# atmega16u2custom2.net
KiCad netlist of a schematic drawn in EAGLE
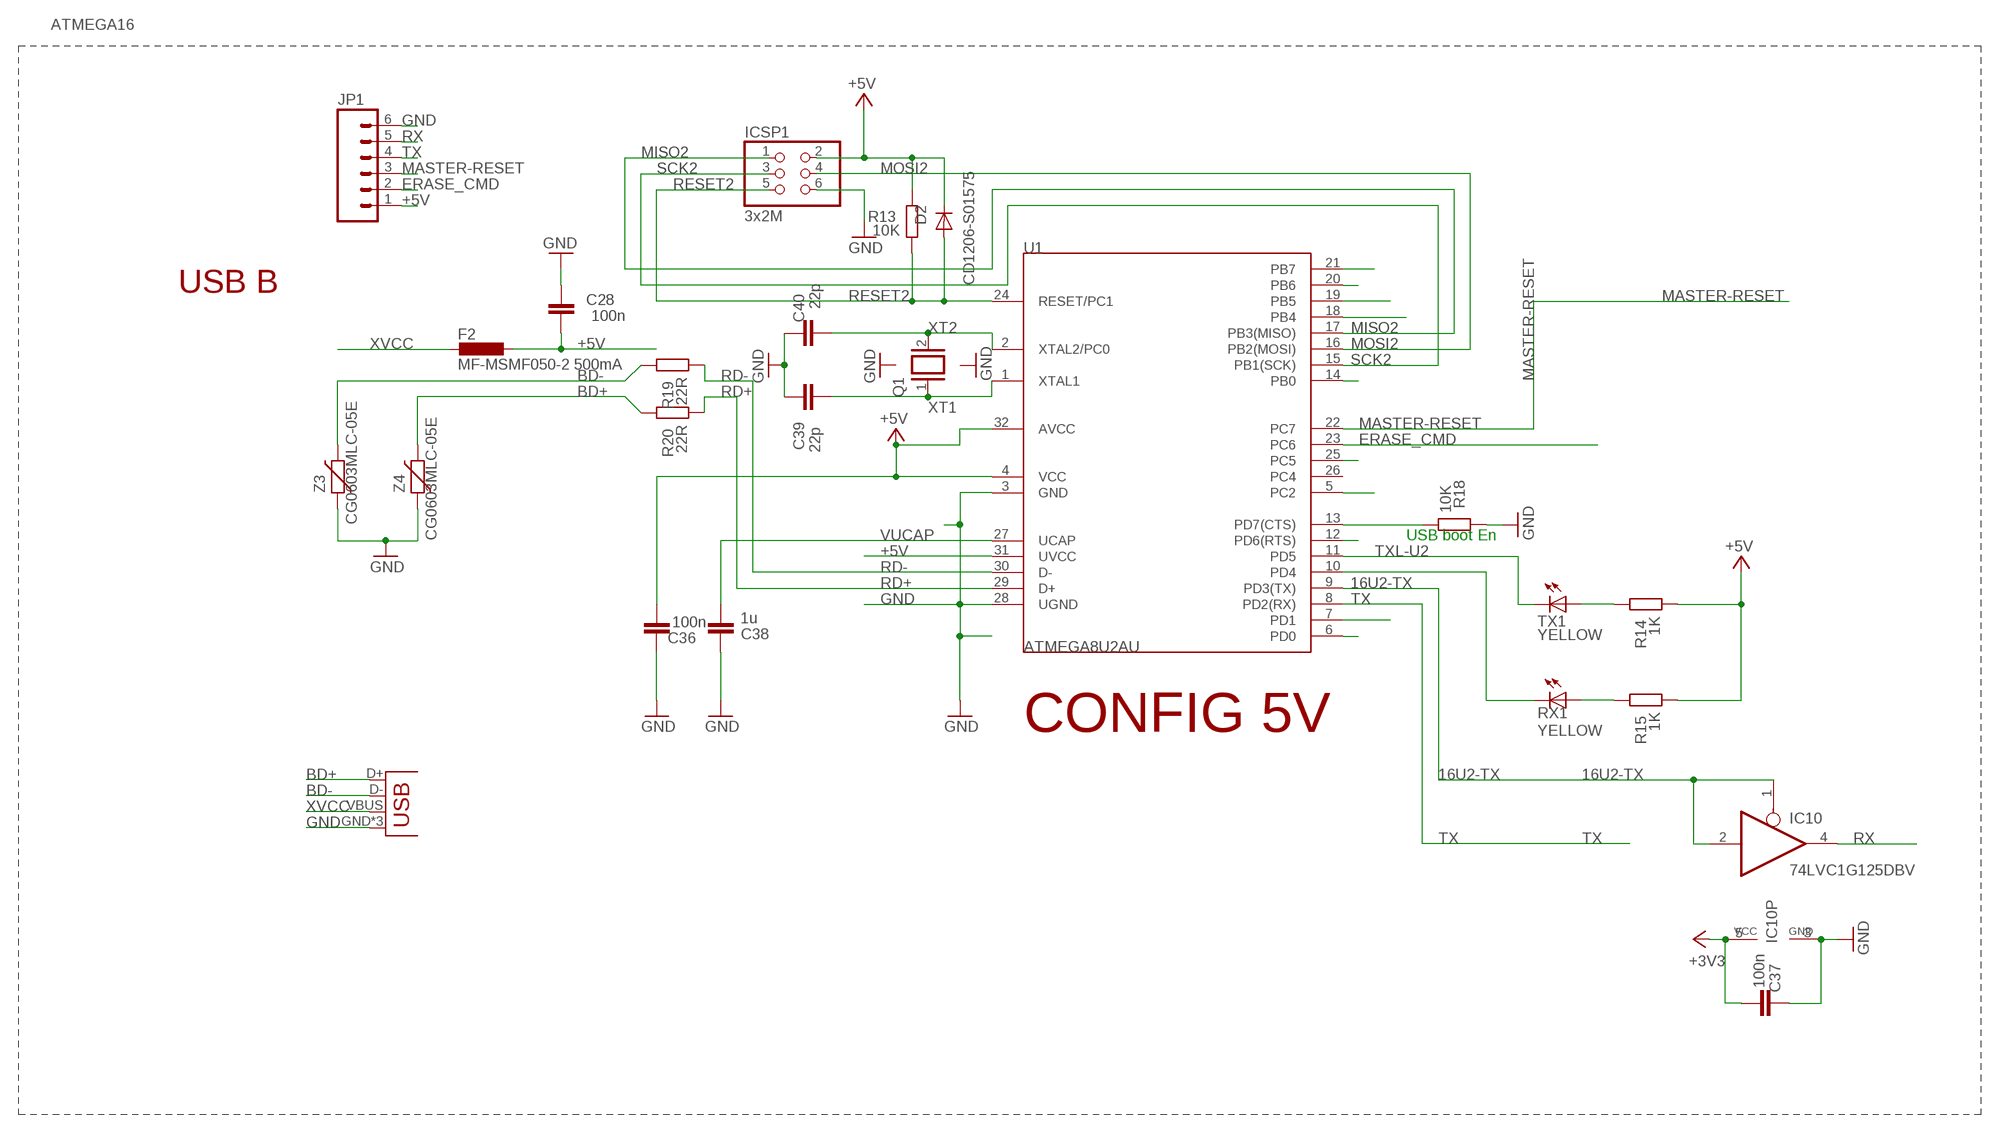
[diagram p0: schematic, sheet 1]

(export (version "E")
  (design (tool "Eeschema 10.0.6"))
  (components
    (comp (ref "C28")
      (value "100n")
      (footprint "eagle-import:C0805")
      (libsource (lib "eagle-import") (part "C-EUC0805"))
    )
    (comp (ref "C36")
      (value "100n")
      (footprint "eagle-import:C0805")
      (libsource (lib "eagle-import") (part "C-EUC0805"))
    )
    (comp (ref "C37")
      (value "100n")
      (footprint "eagle-import:C0805")
      (libsource (lib "eagle-import") (part "C-EUC0805"))
    )
    (comp (ref "C38")
      (value "1u")
      (footprint "eagle-import:C0805")
      (libsource (lib "eagle-import") (part "C-EUC0805"))
    )
    (comp (ref "C39")
      (value "22p")
      (footprint "eagle-import:C0805")
      (libsource (lib "eagle-import") (part "C-EUC0805"))
    )
    (comp (ref "C40")
      (value "22p")
      (footprint "eagle-import:C0805")
      (libsource (lib "eagle-import") (part "C-EUC0805"))
    )
    (comp (ref "D2")
      (value "CD1206-S01575")
      (footprint "eagle-import:MINIMELF")
      (libsource (lib "eagle-import") (part "DIODE-MINIMELF"))
    )
    (comp (ref "F2")
      (value "MF-MSMF050-2 500mA")
      (footprint "eagle-import:L1812")
      (libsource (lib "eagle-import") (part "L-EUL1812"))
    )
    (comp (ref "IC10")
      (value "74LVC1G125DBV")
      (footprint "eagle-import:SOT23-5")
      (libsource (lib "eagle-import") (part "741G125DBVLVC"))
    )
    (comp (ref "ICSP1")
      (value "3x2M")
      (footprint "eagle-import:2X03")
      (libsource (lib "eagle-import") (part "PINHD-2X3"))
    )
    (comp (ref "JP1")
      (value "M06NO_SILK")
      (footprint "eagle-import:1X06_NO_SILK")
      (libsource (lib "eagle-import") (part "M06NO_SILK"))
    )
    (comp (ref "JP2")
      (value "USB-MICROB")
      (footprint "eagle-import:USB-MICROB")
      (libsource (lib "eagle-import") (part "USB-MICROB"))
    )
    (comp (ref "Q1")
      (value "XTAL/S")
      (footprint "eagle-import:QS")
      (libsource (lib "eagle-import") (part "XTAL/S"))
    )
    (comp (ref "R13")
      (value "10K")
      (footprint "eagle-import:R0805")
      (libsource (lib "eagle-import") (part "R-EU_R0805"))
    )
    (comp (ref "R14")
      (value "1K")
      (footprint "eagle-import:R0805")
      (libsource (lib "eagle-import") (part "R-EU_R0805"))
    )
    (comp (ref "R15")
      (value "1K")
      (footprint "eagle-import:R0805")
      (libsource (lib "eagle-import") (part "R-EU_R0805"))
    )
    (comp (ref "R18")
      (value "10K")
      (footprint "eagle-import:R0805")
      (libsource (lib "eagle-import") (part "R-EU_R0805"))
    )
    (comp (ref "R19")
      (value "22R")
      (footprint "eagle-import:R0805")
      (libsource (lib "eagle-import") (part "R-EU_R0805"))
    )
    (comp (ref "R20")
      (value "22R")
      (footprint "eagle-import:R0805")
      (libsource (lib "eagle-import") (part "R-EU_R0805"))
    )
    (comp (ref "RX1")
      (value "YELLOW")
      (footprint "eagle-import:CHIP-LED0805")
      (libsource (lib "eagle-import") (part "LEDCHIP-LED0805"))
    )
    (comp (ref "TX1")
      (value "YELLOW")
      (footprint "eagle-import:CHIP-LED0805")
      (libsource (lib "eagle-import") (part "LEDCHIP-LED0805"))
    )
    (comp (ref "U1")
      (value "ATMEGA8U2AU")
      (footprint "eagle-import:TQFP32-08")
      (libsource (lib "eagle-import") (part "ATMEGA8U2AU"))
    )
    (comp (ref "Z3")
      (value "CG0603MLC-05E")
      (footprint "eagle-import:CT_CN0603")
      (libsource (lib "eagle-import") (part "VARISTORCN0603"))
    )
    (comp (ref "Z4")
      (value "CG0603MLC-05E")
      (footprint "eagle-import:CT_CN0603")
      (libsource (lib "eagle-import") (part "VARISTORCN0603"))
    )
  )
  (nets
    (net (code "1") (name "+3V3") (class "Default")
      (node (ref "C37") (pin "1") (pinfunction "1_1") (pintype "passive"))
      (node (ref "IC10") (pin "5") (pinfunction "VCC_5") (pintype "power_in"))
    )
    (net (code "2") (name "+5V") (class "Default")
      (node (ref "C28") (pin "1") (pinfunction "1_1") (pintype "passive"))
      (node (ref "C36") (pin "1") (pinfunction "1_1") (pintype "passive"))
      (node (ref "D2") (pin "C") (pinfunction "C_C") (pintype "passive"))
      (node (ref "F2") (pin "1") (pinfunction "1_1") (pintype "passive"))
      (node (ref "ICSP1") (pin "2") (pinfunction "2_2") (pintype "passive"))
      (node (ref "JP1") (pin "1") (pinfunction "1_1") (pintype "passive"))
      (node (ref "R13") (pin "2") (pinfunction "2_2") (pintype "passive"))
      (node (ref "R14") (pin "1") (pinfunction "1_1") (pintype "passive"))
      (node (ref "R15") (pin "1") (pinfunction "1_1") (pintype "passive"))
      (node (ref "U1") (pin "31") (pinfunction "UVCC_31") (pintype "bidirectional"))
      (node (ref "U1") (pin "32") (pinfunction "AVCC_32") (pintype "bidirectional"))
      (node (ref "U1") (pin "4") (pinfunction "VCC_4") (pintype "bidirectional"))
    )
    (net (code "3") (name "/16U2-TX") (class "Default")
      (node (ref "IC10") (pin "1") (pinfunction "OE_1") (pintype "input"))
      (node (ref "IC10") (pin "2") (pinfunction "I_2") (pintype "input"))
      (node (ref "U1") (pin "9") (pinfunction "PD3(TX)_9") (pintype "bidirectional"))
    )
    (net (code "4") (name "/BD+") (class "Default")
      (node (ref "JP2") (pin "D+") (pinfunction "D+_D+") (pintype "bidirectional"))
      (node (ref "R20") (pin "2") (pinfunction "2_2") (pintype "passive"))
      (node (ref "Z4") (pin "2") (pinfunction "2_2") (pintype "passive"))
    )
    (net (code "5") (name "/BD-") (class "Default")
      (node (ref "JP2") (pin "D-") (pinfunction "D-_D-") (pintype "bidirectional"))
      (node (ref "R19") (pin "2") (pinfunction "2_2") (pintype "passive"))
      (node (ref "Z3") (pin "2") (pinfunction "2_2") (pintype "passive"))
    )
    (net (code "6") (name "/ERASE_CMD") (class "Default")
      (node (ref "JP1") (pin "2") (pinfunction "2_2") (pintype "passive"))
      (node (ref "U1") (pin "23") (pinfunction "PC6_23") (pintype "bidirectional"))
    )
    (net (code "7") (name "/MASTER-RESET") (class "Default")
      (node (ref "JP1") (pin "3") (pinfunction "3_3") (pintype "passive"))
      (node (ref "U1") (pin "22") (pinfunction "PC7_22") (pintype "bidirectional"))
    )
    (net (code "8") (name "/MISO2") (class "Default")
      (node (ref "ICSP1") (pin "1") (pinfunction "1_1") (pintype "passive"))
      (node (ref "U1") (pin "17") (pinfunction "PB3(MISO)_17") (pintype "bidirectional"))
    )
    (net (code "9") (name "/MOSI2") (class "Default")
      (node (ref "ICSP1") (pin "4") (pinfunction "4_4") (pintype "passive"))
      (node (ref "U1") (pin "16") (pinfunction "PB2(MOSI)_16") (pintype "bidirectional"))
    )
    (net (code "10") (name "/RD+") (class "Default")
      (node (ref "R20") (pin "1") (pinfunction "1_1") (pintype "passive"))
      (node (ref "U1") (pin "29") (pinfunction "D+_29") (pintype "bidirectional"))
    )
    (net (code "11") (name "/RD-") (class "Default")
      (node (ref "R19") (pin "1") (pinfunction "1_1") (pintype "passive"))
      (node (ref "U1") (pin "30") (pinfunction "D-_30") (pintype "bidirectional"))
    )
    (net (code "12") (name "/RESET2") (class "Default")
      (node (ref "D2") (pin "A") (pinfunction "A_A") (pintype "passive"))
      (node (ref "ICSP1") (pin "5") (pinfunction "5_5") (pintype "passive"))
      (node (ref "R13") (pin "1") (pinfunction "1_1") (pintype "passive"))
      (node (ref "U1") (pin "24") (pinfunction "RESET/PC1_24") (pintype "bidirectional"))
    )
    (net (code "13") (name "/RX") (class "Default")
      (node (ref "IC10") (pin "4") (pinfunction "O_4") (pintype "tri_state"))
      (node (ref "JP1") (pin "5") (pinfunction "5_5") (pintype "passive"))
    )
    (net (code "14") (name "/SCK2") (class "Default")
      (node (ref "ICSP1") (pin "3") (pinfunction "3_3") (pintype "passive"))
      (node (ref "U1") (pin "15") (pinfunction "PB1(SCK)_15") (pintype "bidirectional"))
    )
    (net (code "15") (name "/TX") (class "Default")
      (node (ref "JP1") (pin "4") (pinfunction "4_4") (pintype "passive"))
      (node (ref "U1") (pin "8") (pinfunction "PD2(RX)_8") (pintype "bidirectional"))
    )
    (net (code "16") (name "/TXL-U2") (class "Default")
      (node (ref "TX1") (pin "C") (pinfunction "C_C") (pintype "passive"))
      (node (ref "U1") (pin "11") (pinfunction "PD5_11") (pintype "bidirectional"))
    )
    (net (code "17") (name "/VUCAP") (class "Default")
      (node (ref "C38") (pin "1") (pinfunction "1_1") (pintype "passive"))
      (node (ref "U1") (pin "27") (pinfunction "UCAP_27") (pintype "bidirectional"))
    )
    (net (code "18") (name "/XT1") (class "Default")
      (node (ref "C39") (pin "1") (pinfunction "1_1") (pintype "passive"))
      (node (ref "Q1") (pin "1") (pinfunction "1_1") (pintype "passive"))
      (node (ref "U1") (pin "1") (pinfunction "XTAL1_1") (pintype "bidirectional"))
    )
    (net (code "19") (name "/XT2") (class "Default")
      (node (ref "C40") (pin "1") (pinfunction "1_1") (pintype "passive"))
      (node (ref "Q1") (pin "2") (pinfunction "2_2") (pintype "passive"))
      (node (ref "U1") (pin "2") (pinfunction "XTAL2/PC0_2") (pintype "bidirectional"))
    )
    (net (code "20") (name "/XVCC") (class "Default")
      (node (ref "F2") (pin "2") (pinfunction "2_2") (pintype "passive"))
      (node (ref "JP2") (pin "VBUS") (pinfunction "VBUS_VBUS") (pintype "bidirectional"))
    )
    (net (code "21") (name "GND") (class "Default")
      (node (ref "C28") (pin "2") (pinfunction "2_2") (pintype "passive"))
      (node (ref "C36") (pin "2") (pinfunction "2_2") (pintype "passive"))
      (node (ref "C37") (pin "2") (pinfunction "2_2") (pintype "passive"))
      (node (ref "C38") (pin "2") (pinfunction "2_2") (pintype "passive"))
      (node (ref "C39") (pin "2") (pinfunction "2_2") (pintype "passive"))
      (node (ref "C40") (pin "2") (pinfunction "2_2") (pintype "passive"))
      (node (ref "IC10") (pin "3") (pinfunction "GND_3") (pintype "power_in"))
      (node (ref "ICSP1") (pin "6") (pinfunction "6_6") (pintype "passive"))
      (node (ref "JP1") (pin "6") (pinfunction "6_6") (pintype "passive"))
      (node (ref "JP2") (pin "GND") (pinfunction "GND_GND") (pintype "bidirectional"))
      (node (ref "JP2") (pin "MT1") (pinfunction "GND_MT1") (pintype "bidirectional"))
      (node (ref "JP2") (pin "MT2") (pinfunction "GND_MT2") (pintype "bidirectional"))
      (node (ref "R18") (pin "2") (pinfunction "2_2") (pintype "passive"))
      (node (ref "U1") (pin "28") (pinfunction "UGND_28") (pintype "bidirectional"))
      (node (ref "U1") (pin "3") (pinfunction "GND_3") (pintype "bidirectional"))
      (node (ref "Z3") (pin "1") (pinfunction "1_1") (pintype "passive"))
      (node (ref "Z4") (pin "1") (pinfunction "1_1") (pintype "passive"))
    )
    (net (code "22") (name "Net-(R14-Pad2)") (class "Default")
      (node (ref "R14") (pin "2") (pinfunction "2_2") (pintype "passive"))
      (node (ref "TX1") (pin "A") (pinfunction "A_A") (pintype "passive"))
    )
    (net (code "23") (name "Net-(R15-Pad2)") (class "Default")
      (node (ref "R15") (pin "2") (pinfunction "2_2") (pintype "passive"))
      (node (ref "RX1") (pin "A") (pinfunction "A_A") (pintype "passive"))
    )
    (net (code "24") (name "Net-(U1-PD4)") (class "Default")
      (node (ref "RX1") (pin "C") (pinfunction "C_C") (pintype "passive"))
      (node (ref "U1") (pin "10") (pinfunction "PD4_10") (pintype "bidirectional"))
    )
    (net (code "25") (name "Net-(U1-PD7(CTS))") (class "Default")
      (node (ref "R18") (pin "1") (pinfunction "1_1") (pintype "passive"))
      (node (ref "U1") (pin "13") (pinfunction "PD7(CTS)_13") (pintype "bidirectional"))
    )
    (net (code "26") (name "unconnected-(U1-PB0-Pad14)") (class "Default")
      (node (ref "U1") (pin "14") (pinfunction "PB0_14") (pintype "bidirectional"))
    )
    (net (code "27") (name "unconnected-(U1-PB4-Pad18)") (class "Default")
      (node (ref "U1") (pin "18") (pinfunction "PB4_18") (pintype "bidirectional"))
    )
    (net (code "28") (name "unconnected-(U1-PB5-Pad19)") (class "Default")
      (node (ref "U1") (pin "19") (pinfunction "PB5_19") (pintype "bidirectional"))
    )
    (net (code "29") (name "unconnected-(U1-PB6-Pad20)") (class "Default")
      (node (ref "U1") (pin "20") (pinfunction "PB6_20") (pintype "bidirectional"))
    )
    (net (code "30") (name "unconnected-(U1-PB7-Pad21)") (class "Default")
      (node (ref "U1") (pin "21") (pinfunction "PB7_21") (pintype "bidirectional"))
    )
    (net (code "31") (name "unconnected-(U1-PC2-Pad5)") (class "Default")
      (node (ref "U1") (pin "5") (pinfunction "PC2_5") (pintype "bidirectional"))
    )
    (net (code "32") (name "unconnected-(U1-PC4-Pad26)") (class "Default")
      (node (ref "U1") (pin "26") (pinfunction "PC4_26") (pintype "bidirectional"))
    )
    (net (code "33") (name "unconnected-(U1-PC5-Pad25)") (class "Default")
      (node (ref "U1") (pin "25") (pinfunction "PC5_25") (pintype "bidirectional"))
    )
    (net (code "34") (name "unconnected-(U1-PD0-Pad6)") (class "Default")
      (node (ref "U1") (pin "6") (pinfunction "PD0_6") (pintype "bidirectional"))
    )
    (net (code "35") (name "unconnected-(U1-PD1-Pad7)") (class "Default")
      (node (ref "U1") (pin "7") (pinfunction "PD1_7") (pintype "bidirectional"))
    )
    (net (code "36") (name "unconnected-(U1-PD6(RTS)-Pad12)") (class "Default")
      (node (ref "U1") (pin "12") (pinfunction "PD6(RTS)_12") (pintype "bidirectional"))
    )
  )
)
